# Cameras.net
KiCad netlist of a schematic drawn in Altium Designer
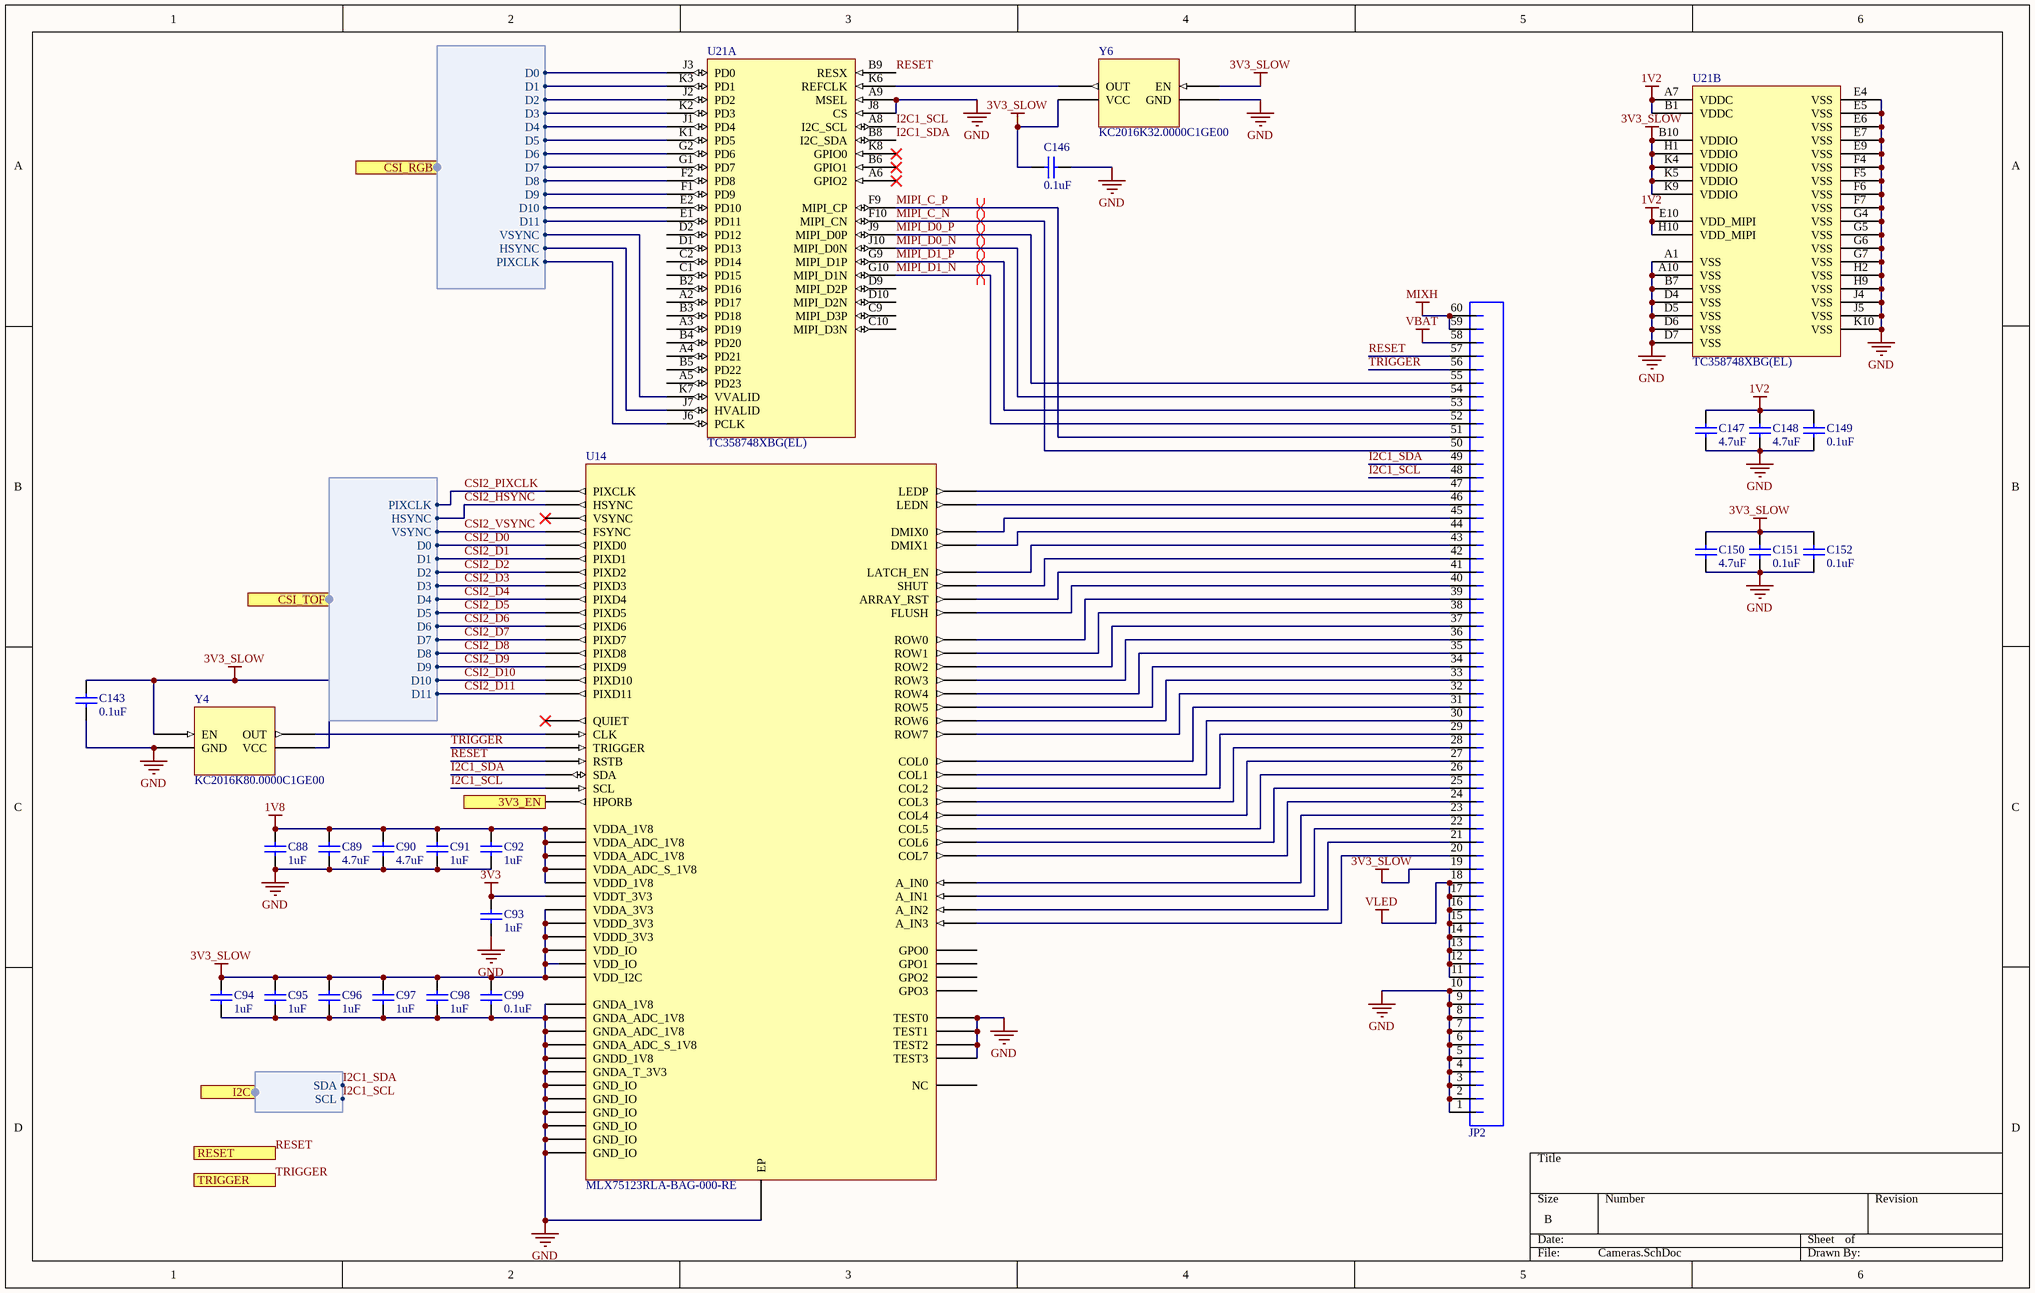
[diagram p0: Cameras.SchDoc]

(export (version "E")
  (design (tool "Eeschema 10.0.6"))
  (components
    (comp (ref "C88")
      (value "1uF")
      (footprint "C0402[1005X55]")
      (description "1uF 6.3V 10% 0402 (1005 Metric)")
      (fields (field (name "PARTNUMBER") "GRM155R70J105KA12D") (field (name "MANUFACTURER") "Murata"))
      (libsource (lib "Capacitors") (part "CAP_1uF_6.3V_0402_10%"))
    )
    (comp (ref "C89")
      (value "4.7uF")
      (footprint "C0402[1005X55]")
      (description "4.7uF 6.3V 20% 0402 (1005 Metric)")
      (fields (field (name "PARTNUMBER") "GRM155R60J475ME47D") (field (name "MANUFACTURER") "Murata"))
      (libsource (lib "Capacitors") (part "CAP_4.7uF_6.3V_0402_20%"))
    )
    (comp (ref "C90")
      (value "4.7uF")
      (footprint "C0402[1005X55]")
      (description "4.7uF 6.3V 20% 0402 (1005 Metric)")
      (fields (field (name "PARTNUMBER") "GRM155R60J475ME47D") (field (name "MANUFACTURER") "Murata"))
      (libsource (lib "Capacitors") (part "CAP_4.7uF_6.3V_0402_20%"))
    )
    (comp (ref "C91")
      (value "1uF")
      (footprint "C0402[1005X55]")
      (description "1uF 6.3V 10% 0402 (1005 Metric)")
      (fields (field (name "PARTNUMBER") "GRM155R70J105KA12D") (field (name "MANUFACTURER") "Murata"))
      (libsource (lib "Capacitors") (part "CAP_1uF_6.3V_0402_10%"))
    )
    (comp (ref "C92")
      (value "1uF")
      (footprint "C0402[1005X55]")
      (description "1uF 6.3V 10% 0402 (1005 Metric)")
      (fields (field (name "PARTNUMBER") "GRM155R70J105KA12D") (field (name "MANUFACTURER") "Murata"))
      (libsource (lib "Capacitors") (part "CAP_1uF_6.3V_0402_10%"))
    )
    (comp (ref "C93")
      (value "1uF")
      (footprint "C0402[1005X55]")
      (description "1uF 6.3V 10% 0402 (1005 Metric)")
      (fields (field (name "PARTNUMBER") "GRM155R70J105KA12D") (field (name "MANUFACTURER") "Murata"))
      (libsource (lib "Capacitors") (part "CAP_1uF_6.3V_0402_10%"))
    )
    (comp (ref "C94")
      (value "1uF")
      (footprint "C0402[1005X55]")
      (description "1uF 6.3V 10% 0402 (1005 Metric)")
      (fields (field (name "PARTNUMBER") "GRM155R70J105KA12D") (field (name "MANUFACTURER") "Murata"))
      (libsource (lib "Capacitors") (part "CAP_1uF_6.3V_0402_10%"))
    )
    (comp (ref "C95")
      (value "1uF")
      (footprint "C0402[1005X55]")
      (description "1uF 6.3V 10% 0402 (1005 Metric)")
      (fields (field (name "PARTNUMBER") "GRM155R70J105KA12D") (field (name "MANUFACTURER") "Murata"))
      (libsource (lib "Capacitors") (part "CAP_1uF_6.3V_0402_10%"))
    )
    (comp (ref "C96")
      (value "1uF")
      (footprint "C0402[1005X55]")
      (description "1uF 6.3V 10% 0402 (1005 Metric)")
      (fields (field (name "PARTNUMBER") "GRM155R70J105KA12D") (field (name "MANUFACTURER") "Murata"))
      (libsource (lib "Capacitors") (part "CAP_1uF_6.3V_0402_10%"))
    )
    (comp (ref "C97")
      (value "1uF")
      (footprint "C0402[1005X55]")
      (description "1uF 6.3V 10% 0402 (1005 Metric)")
      (fields (field (name "PARTNUMBER") "GRM155R70J105KA12D") (field (name "MANUFACTURER") "Murata"))
      (libsource (lib "Capacitors") (part "CAP_1uF_6.3V_0402_10%"))
    )
    (comp (ref "C98")
      (value "1uF")
      (footprint "C0402[1005X55]")
      (description "1uF 6.3V 10% 0402 (1005 Metric)")
      (fields (field (name "PARTNUMBER") "GRM155R70J105KA12D") (field (name "MANUFACTURER") "Murata"))
      (libsource (lib "Capacitors") (part "CAP_1uF_6.3V_0402_10%"))
    )
    (comp (ref "C99")
      (value "0.1uF")
      (footprint "C0402[1005X55]")
      (description "0.1uF 6.3V 10% 0402 (1005 Metric)")
      (fields (field (name "PARTNUMBER") "GRM155R70J104KA01D") (field (name "MANUFACTURER") "Murata"))
      (libsource (lib "Capacitors") (part "CAP_0.1uF_6.3V_0402_10%"))
    )
    (comp (ref "C143")
      (value "0.1uF")
      (footprint "C0402[1005X55]")
      (description "0.1uF 6.3V 10% 0402 (1005 Metric)")
      (fields (field (name "PARTNUMBER") "GRM155R70J104KA01D") (field (name "MANUFACTURER") "Murata"))
      (libsource (lib "Capacitors") (part "CAP_0.1uF_6.3V_0402_10%"))
    )
    (comp (ref "C146")
      (value "0.1uF")
      (footprint "C0402[1005X55]")
      (description "0.1uF 6.3V 10% 0402 (1005 Metric)")
      (fields (field (name "PARTNUMBER") "GRM155R70J104KA01D") (field (name "MANUFACTURER") "Murata"))
      (libsource (lib "Capacitors") (part "CAP_0.1uF_6.3V_0402_10%"))
    )
    (comp (ref "C147")
      (value "4.7uF")
      (footprint "C0402[1005X55]")
      (description "4.7uF 6.3V 20% 0402 (1005 Metric)")
      (fields (field (name "PARTNUMBER") "GRM155R60J475ME47D") (field (name "MANUFACTURER") "Murata"))
      (libsource (lib "Capacitors") (part "CAP_4.7uF_6.3V_0402_20%"))
    )
    (comp (ref "C148")
      (value "4.7uF")
      (footprint "C0402[1005X55]")
      (description "4.7uF 6.3V 20% 0402 (1005 Metric)")
      (fields (field (name "PARTNUMBER") "GRM155R60J475ME47D") (field (name "MANUFACTURER") "Murata"))
      (libsource (lib "Capacitors") (part "CAP_4.7uF_6.3V_0402_20%"))
    )
    (comp (ref "C149")
      (value "0.1uF")
      (footprint "C0402[1005X55]")
      (description "0.1uF 6.3V 10% 0402 (1005 Metric)")
      (fields (field (name "PARTNUMBER") "GRM155R70J104KA01D") (field (name "MANUFACTURER") "Murata"))
      (libsource (lib "Capacitors") (part "CAP_0.1uF_6.3V_0402_10%"))
    )
    (comp (ref "C150")
      (value "4.7uF")
      (footprint "C0402[1005X55]")
      (description "4.7uF 6.3V 20% 0402 (1005 Metric)")
      (fields (field (name "PARTNUMBER") "GRM155R60J475ME47D") (field (name "MANUFACTURER") "Murata"))
      (libsource (lib "Capacitors") (part "CAP_4.7uF_6.3V_0402_20%"))
    )
    (comp (ref "C151")
      (value "0.1uF")
      (footprint "C0402[1005X55]")
      (description "0.1uF 6.3V 10% 0402 (1005 Metric)")
      (fields (field (name "PARTNUMBER") "GRM155R70J104KA01D") (field (name "MANUFACTURER") "Murata"))
      (libsource (lib "Capacitors") (part "CAP_0.1uF_6.3V_0402_10%"))
    )
    (comp (ref "C152")
      (value "0.1uF")
      (footprint "C0402[1005X55]")
      (description "0.1uF 6.3V 10% 0402 (1005 Metric)")
      (fields (field (name "PARTNUMBER") "GRM155R70J104KA01D") (field (name "MANUFACTURER") "Murata"))
      (libsource (lib "Capacitors") (part "CAP_0.1uF_6.3V_0402_10%"))
    )
    (comp (ref "JP2")
      (value "JST_JMD_60_HORZ")
      (footprint "JST-JMD-60-SMD-HORZ")
      (fields
        (field (name "MANUFACTURER") "JST Sales America, Inc.")
        (field (name "PARTNUMBER") "60PS-JMDSS-G-1-TF")
      )
      (libsource (lib "Connectors") (part "JST_JMD_60_HORZ"))
    )
    (comp (ref "U14")
      (value "MLX75123RLA-BAG-000-RE")
      (footprint "AQFN-84")
      (description "Sensor Interface ToF Companion Chip")
      (fields (field (name "MANUFACTURER") "Melexis"))
      (libsource (lib "ICs") (part "MLX75123RLA-BAG-000-RE"))
    )
    (comp (ref "U21")
      (value "TC358748XBG(EL)")
      (footprint "BGA-80")
      (description "IC MIPI CSI2 TO PARALLEL 80VFBGA")
      (fields (field (name "MANUFACTURER") "Toshiba Semiconductor"))
      (libsource (lib "ICs") (part "TC358748XBG(EL)"))
    )
    (comp (ref "Y4")
      (value "KC2016K80.0000C1GE00")
      (footprint "KC2016K")
      (description "OSC XO 80.0000MHZ CMOS SMD")
      (fields (field (name "MANUFACTURER") "AVX"))
      (libsource (lib "Components") (part "KC2016K80.0000C1GE00"))
    )
    (comp (ref "Y6")
      (value "KC2016K32.0000C1GE00")
      (footprint "KC2016K")
      (description "OSC XO 32.0000MHZ CMOS SMD")
      (fields (field (name "MANUFACTURER") "Kyocera"))
      (libsource (lib "Components") (part "KC2016K32.0000C1GE00"))
    )
  )
  (nets
    (net (code "3") (name "/3V3_EN") (class "Default")
      (node (ref "U14") (pin "A19") (pinfunction "HPORB_A19") (pintype "output"))
    )
    (net (code "4") (name "/CSI2_D0") (class "Default")
      (node (ref "U14") (pin "A30") (pinfunction "PIXD0_A30") (pintype "output"))
    )
    (net (code "5") (name "/CSI2_D1") (class "Default")
      (node (ref "U14") (pin "B27") (pinfunction "PIXD1_B27") (pintype "output"))
    )
    (net (code "6") (name "/CSI2_D2") (class "Default")
      (node (ref "U14") (pin "A29") (pinfunction "PIXD2_A29") (pintype "output"))
    )
    (net (code "7") (name "/CSI2_D3") (class "Default")
      (node (ref "U14") (pin "B26") (pinfunction "PIXD3_B26") (pintype "output"))
    )
    (net (code "8") (name "/CSI2_D4") (class "Default")
      (node (ref "U14") (pin "A28") (pinfunction "PIXD4_A28") (pintype "output"))
    )
    (net (code "9") (name "/CSI2_D5") (class "Default")
      (node (ref "U14") (pin "B25") (pinfunction "PIXD5_B25") (pintype "output"))
    )
    (net (code "10") (name "/CSI2_D6") (class "Default")
      (node (ref "U14") (pin "A27") (pinfunction "PIXD6_A27") (pintype "output"))
    )
    (net (code "11") (name "/CSI2_D7") (class "Default")
      (node (ref "U14") (pin "B24") (pinfunction "PIXD7_B24") (pintype "output"))
    )
    (net (code "12") (name "/CSI2_D8") (class "Default")
      (node (ref "U14") (pin "A26") (pinfunction "PIXD8_A26") (pintype "output"))
    )
    (net (code "13") (name "/CSI2_D9") (class "Default")
      (node (ref "U14") (pin "B23") (pinfunction "PIXD9_B23") (pintype "output"))
    )
    (net (code "14") (name "/CSI2_D10") (class "Default")
      (node (ref "U14") (pin "A25") (pinfunction "PIXD10_A25") (pintype "output"))
    )
    (net (code "15") (name "/CSI2_D11") (class "Default")
      (node (ref "U14") (pin "B22") (pinfunction "PIXD11_B22") (pintype "output"))
    )
    (net (code "16") (name "/CSI2_HSYNC") (class "Default")
      (node (ref "U14") (pin "B29") (pinfunction "HSYNC_B29") (pintype "output"))
    )
    (net (code "17") (name "/CSI2_PIXCLK") (class "Default")
      (node (ref "U14") (pin "B28") (pinfunction "PIXCLK_B28") (pintype "output"))
    )
    (net (code "18") (name "/CSI2_VSYNC") (class "Default")
      (node (ref "U14") (pin "A31") (pinfunction "FSYNC_A31") (pintype "output"))
    )
    (net (code "19") (name "/I2C1_SCL") (class "Default")
      (node (ref "JP2") (pin "48") (pinfunction "48_48") (pintype "passive"))
      (node (ref "U14") (pin "A12") (pinfunction "SCL_A12") (pintype "input"))
      (node (ref "U21") (pin "A8") (pinfunction "I2C_SCL_A8") (pintype "bidirectional"))
    )
    (net (code "20") (name "/I2C1_SDA") (class "Default")
      (node (ref "JP2") (pin "49") (pinfunction "49_49") (pintype "passive"))
      (node (ref "U14") (pin "B11") (pinfunction "SDA_B11") (pintype "bidirectional"))
      (node (ref "U21") (pin "B8") (pinfunction "I2C_SDA_B8") (pintype "bidirectional"))
    )
    (net (code "21") (name "/MIPI_C_N") (class "Default")
      (node (ref "JP2") (pin "50") (pinfunction "50_50") (pintype "passive"))
      (node (ref "U21") (pin "F10") (pinfunction "MIPI_CN_F10") (pintype "bidirectional"))
    )
    (net (code "22") (name "/MIPI_C_P") (class "Default")
      (node (ref "JP2") (pin "51") (pinfunction "51_51") (pintype "passive"))
      (node (ref "U21") (pin "F9") (pinfunction "MIPI_CP_F9") (pintype "bidirectional"))
    )
    (net (code "23") (name "/MIPI_D0_N") (class "Default")
      (node (ref "JP2") (pin "54") (pinfunction "54_54") (pintype "passive"))
      (node (ref "U21") (pin "J10") (pinfunction "MIPI_D0N_J10") (pintype "bidirectional"))
    )
    (net (code "24") (name "/MIPI_D0_P") (class "Default")
      (node (ref "JP2") (pin "55") (pinfunction "55_55") (pintype "passive"))
      (node (ref "U21") (pin "J9") (pinfunction "MIPI_D0P_J9") (pintype "bidirectional"))
    )
    (net (code "25") (name "/MIPI_D1_N") (class "Default")
      (node (ref "JP2") (pin "52") (pinfunction "52_52") (pintype "passive"))
      (node (ref "U21") (pin "G10") (pinfunction "MIPI_D1N_G10") (pintype "bidirectional"))
    )
    (net (code "26") (name "/MIPI_D1_P") (class "Default")
      (node (ref "JP2") (pin "53") (pinfunction "53_53") (pintype "passive"))
      (node (ref "U21") (pin "G9") (pinfunction "MIPI_D1P_G9") (pintype "bidirectional"))
    )
    (net (code "27") (name "/RESET") (class "Default")
      (node (ref "JP2") (pin "57") (pinfunction "57_57") (pintype "passive"))
      (node (ref "U14") (pin "A14") (pinfunction "RSTB_A14") (pintype "input"))
      (node (ref "U21") (pin "B9") (pinfunction "RESX_B9") (pintype "input"))
    )
    (net (code "28") (name "/TRIGGER") (class "Default")
      (node (ref "JP2") (pin "56") (pinfunction "56_56") (pintype "passive"))
      (node (ref "U14") (pin "A13") (pinfunction "TRIGGER_A13") (pintype "input"))
    )
    (net (code "31") (name "1V2") (class "Default")
      (node (ref "C147") (pin "2") (pinfunction "2_2") (pintype "passive"))
      (node (ref "C148") (pin "2") (pinfunction "2_2") (pintype "passive"))
      (node (ref "C149") (pin "2") (pinfunction "2_2") (pintype "passive"))
      (node (ref "U21") (pin "A7") (pinfunction "VDDC_A7") (pintype "power_in"))
      (node (ref "U21") (pin "B1") (pinfunction "VDDC_B1") (pintype "power_in"))
      (node (ref "U21") (pin "E10") (pinfunction "VDD_MIPI_E10") (pintype "power_in"))
      (node (ref "U21") (pin "H10") (pinfunction "VDD_MIPI_H10") (pintype "power_in"))
    )
    (net (code "32") (name "1V8") (class "Default")
      (node (ref "C88") (pin "2") (pinfunction "2_2") (pintype "passive"))
      (node (ref "C89") (pin "2") (pinfunction "2_2") (pintype "passive"))
      (node (ref "C90") (pin "2") (pinfunction "2_2") (pintype "passive"))
      (node (ref "C91") (pin "2") (pinfunction "2_2") (pintype "passive"))
      (node (ref "C92") (pin "2") (pinfunction "2_2") (pintype "passive"))
      (node (ref "U14") (pin "A10") (pinfunction "VDDA_ADC_S_1V8_A10") (pintype "power_in"))
      (node (ref "U14") (pin "A9") (pinfunction "VDDA_ADC_1V8_A9") (pintype "power_in"))
      (node (ref "U14") (pin "B14") (pinfunction "VDDA_1V8_B14") (pintype "power_in"))
      (node (ref "U14") (pin "B20") (pinfunction "VDDD_1V8_B20") (pintype "power_in"))
      (node (ref "U14") (pin "B5") (pinfunction "VDDA_ADC_1V8_B5") (pintype "power_in"))
    )
    (net (code "33") (name "3V3") (class "Default")
      (node (ref "C93") (pin "2") (pinfunction "2_2") (pintype "passive"))
      (node (ref "U14") (pin "B17") (pinfunction "VDDT_3V3_B17") (pintype "power_in"))
    )
    (net (code "34") (name "3V3_SLOW") (class "Default")
      (node (ref "C143") (pin "2") (pinfunction "2_2") (pintype "passive"))
      (node (ref "C146") (pin "1") (pinfunction "1_1") (pintype "passive"))
      (node (ref "C150") (pin "2") (pinfunction "2_2") (pintype "passive"))
      (node (ref "C151") (pin "2") (pinfunction "2_2") (pintype "passive"))
      (node (ref "C152") (pin "2") (pinfunction "2_2") (pintype "passive"))
      (node (ref "C94") (pin "2") (pinfunction "2_2") (pintype "passive"))
      (node (ref "C95") (pin "2") (pinfunction "2_2") (pintype "passive"))
      (node (ref "C96") (pin "2") (pinfunction "2_2") (pintype "passive"))
      (node (ref "C97") (pin "2") (pinfunction "2_2") (pintype "passive"))
      (node (ref "C98") (pin "2") (pinfunction "2_2") (pintype "passive"))
      (node (ref "C99") (pin "2") (pinfunction "2_2") (pintype "passive"))
      (node (ref "JP2") (pin "19") (pinfunction "19_19") (pintype "passive"))
      (node (ref "U14") (pin "A36") (pinfunction "VDDD_3V3_A36") (pintype "power_in"))
      (node (ref "U14") (pin "B12") (pinfunction "VDD_I2C_B12") (pintype "power_in"))
      (node (ref "U14") (pin "B21") (pinfunction "VDD_IO_B21") (pintype "power_in"))
      (node (ref "U14") (pin "B30") (pinfunction "VDD_IO_B30") (pintype "power_in"))
      (node (ref "U14") (pin "B38") (pinfunction "VDDD_3V3_B38") (pintype "power_in"))
      (node (ref "U14") (pin "B4") (pinfunction "VDDA_3V3_B4") (pintype "power_in"))
      (node (ref "U21") (pin "B10") (pinfunction "VDDIO_B10") (pintype "power_in"))
      (node (ref "U21") (pin "H1") (pinfunction "VDDIO_H1") (pintype "power_in"))
      (node (ref "U21") (pin "K4") (pinfunction "VDDIO_K4") (pintype "power_in"))
      (node (ref "U21") (pin "K5") (pinfunction "VDDIO_K5") (pintype "power_in"))
      (node (ref "U21") (pin "K9") (pinfunction "VDDIO_K9") (pintype "power_in"))
      (node (ref "Y4") (pin "1") (pinfunction "EN_1") (pintype "input"))
      (node (ref "Y4") (pin "4") (pinfunction "VCC_4") (pintype "power_in"))
      (node (ref "Y6") (pin "1") (pinfunction "EN_1") (pintype "input"))
      (node (ref "Y6") (pin "4") (pinfunction "VCC_4") (pintype "power_in"))
    )
    (net (code "35") (name "GND") (class "Default")
      (node (ref "C143") (pin "1") (pinfunction "1_1") (pintype "passive"))
      (node (ref "C146") (pin "2") (pinfunction "2_2") (pintype "passive"))
      (node (ref "C147") (pin "1") (pinfunction "1_1") (pintype "passive"))
      (node (ref "C148") (pin "1") (pinfunction "1_1") (pintype "passive"))
      (node (ref "C149") (pin "1") (pinfunction "1_1") (pintype "passive"))
      (node (ref "C150") (pin "1") (pinfunction "1_1") (pintype "passive"))
      (node (ref "C151") (pin "1") (pinfunction "1_1") (pintype "passive"))
      (node (ref "C152") (pin "1") (pinfunction "1_1") (pintype "passive"))
      (node (ref "C88") (pin "1") (pinfunction "1_1") (pintype "passive"))
      (node (ref "C89") (pin "1") (pinfunction "1_1") (pintype "passive"))
      (node (ref "C90") (pin "1") (pinfunction "1_1") (pintype "passive"))
      (node (ref "C91") (pin "1") (pinfunction "1_1") (pintype "passive"))
      (node (ref "C92") (pin "1") (pinfunction "1_1") (pintype "passive"))
      (node (ref "C93") (pin "1") (pinfunction "1_1") (pintype "passive"))
      (node (ref "C94") (pin "1") (pinfunction "1_1") (pintype "passive"))
      (node (ref "C95") (pin "1") (pinfunction "1_1") (pintype "passive"))
      (node (ref "C96") (pin "1") (pinfunction "1_1") (pintype "passive"))
      (node (ref "C97") (pin "1") (pinfunction "1_1") (pintype "passive"))
      (node (ref "C98") (pin "1") (pinfunction "1_1") (pintype "passive"))
      (node (ref "C99") (pin "1") (pinfunction "1_1") (pintype "passive"))
      (node (ref "JP2") (pin "1") (pinfunction "1_1") (pintype "passive"))
      (node (ref "JP2") (pin "10") (pinfunction "10_10") (pintype "passive"))
      (node (ref "JP2") (pin "2") (pinfunction "2_2") (pintype "passive"))
      (node (ref "JP2") (pin "3") (pinfunction "3_3") (pintype "passive"))
      (node (ref "JP2") (pin "4") (pinfunction "4_4") (pintype "passive"))
      (node (ref "JP2") (pin "5") (pinfunction "5_5") (pintype "passive"))
      (node (ref "JP2") (pin "6") (pinfunction "6_6") (pintype "passive"))
      (node (ref "JP2") (pin "7") (pinfunction "7_7") (pintype "passive"))
      (node (ref "JP2") (pin "8") (pinfunction "8_8") (pintype "passive"))
      (node (ref "JP2") (pin "9") (pinfunction "9_9") (pintype "passive"))
      (node (ref "U14") (pin "A11") (pinfunction "TEST2_A11") (pintype "passive"))
      (node (ref "U14") (pin "A16") (pinfunction "GNDA_1V8_A16") (pintype "power_in"))
      (node (ref "U14") (pin "A17") (pinfunction "TEST0_A17") (pintype "passive"))
      (node (ref "U14") (pin "A18") (pinfunction "GNDA_T_3V3_A18") (pintype "power_in"))
      (node (ref "U14") (pin "A22") (pinfunction "GNDD_1V8_A22") (pintype "power_in"))
      (node (ref "U14") (pin "A24") (pinfunction "GND_IO_A24") (pintype "power_in"))
      (node (ref "U14") (pin "A33") (pinfunction "GND_IO_A33") (pintype "power_in"))
      (node (ref "U14") (pin "A41") (pinfunction "GND_IO_A41") (pintype "power_in"))
      (node (ref "U14") (pin "A5") (pinfunction "GNDA_ADC_1V8_A5") (pintype "power_in"))
      (node (ref "U14") (pin "A8") (pinfunction "GND_IO_A8") (pintype "power_in"))
      (node (ref "U14") (pin "B10") (pinfunction "TEST3_B10") (pintype "passive"))
      (node (ref "U14") (pin "B15") (pinfunction "GND_IO_B15") (pintype "power_in"))
      (node (ref "U14") (pin "B16") (pinfunction "TEST1_B16") (pintype "passive"))
      (node (ref "U14") (pin "B33") (pinfunction "GND_IO_B33") (pintype "power_in"))
      (node (ref "U14") (pin "B8") (pinfunction "GNDA_ADC_1V8_B8") (pintype "power_in"))
      (node (ref "U14") (pin "B9") (pinfunction "GNDA_ADC_S_1V8_B9") (pintype "power_in"))
      (node (ref "U14") (pin "EP") (pinfunction "EP_EP") (pintype "passive"))
      (node (ref "U21") (pin "A1") (pinfunction "VSS_A1") (pintype "power_in"))
      (node (ref "U21") (pin "A10") (pinfunction "VSS_A10") (pintype "power_in"))
      (node (ref "U21") (pin "A9") (pinfunction "MSEL_A9") (pintype "input"))
      (node (ref "U21") (pin "B7") (pinfunction "VSS_B7") (pintype "power_in"))
      (node (ref "U21") (pin "D4") (pinfunction "VSS_D4") (pintype "power_in"))
      (node (ref "U21") (pin "D5") (pinfunction "VSS_D5") (pintype "power_in"))
      (node (ref "U21") (pin "D6") (pinfunction "VSS_D6") (pintype "power_in"))
      (node (ref "U21") (pin "D7") (pinfunction "VSS_D7") (pintype "power_in"))
      (node (ref "U21") (pin "E4") (pinfunction "VSS_E4") (pintype "power_in"))
      (node (ref "U21") (pin "E5") (pinfunction "VSS_E5") (pintype "power_in"))
      (node (ref "U21") (pin "E6") (pinfunction "VSS_E6") (pintype "power_in"))
      (node (ref "U21") (pin "E7") (pinfunction "VSS_E7") (pintype "power_in"))
      (node (ref "U21") (pin "E9") (pinfunction "VSS_E9") (pintype "power_in"))
      (node (ref "U21") (pin "F4") (pinfunction "VSS_F4") (pintype "power_in"))
      (node (ref "U21") (pin "F5") (pinfunction "VSS_F5") (pintype "power_in"))
      (node (ref "U21") (pin "F6") (pinfunction "VSS_F6") (pintype "power_in"))
      (node (ref "U21") (pin "F7") (pinfunction "VSS_F7") (pintype "power_in"))
      (node (ref "U21") (pin "G4") (pinfunction "VSS_G4") (pintype "power_in"))
      (node (ref "U21") (pin "G5") (pinfunction "VSS_G5") (pintype "power_in"))
      (node (ref "U21") (pin "G6") (pinfunction "VSS_G6") (pintype "power_in"))
      (node (ref "U21") (pin "G7") (pinfunction "VSS_G7") (pintype "power_in"))
      (node (ref "U21") (pin "H2") (pinfunction "VSS_H2") (pintype "power_in"))
      (node (ref "U21") (pin "H9") (pinfunction "VSS_H9") (pintype "power_in"))
      (node (ref "U21") (pin "J4") (pinfunction "VSS_J4") (pintype "power_in"))
      (node (ref "U21") (pin "J5") (pinfunction "VSS_J5") (pintype "power_in"))
      (node (ref "U21") (pin "J8") (pinfunction "CS_J8") (pintype "input"))
      (node (ref "U21") (pin "K10") (pinfunction "VSS_K10") (pintype "power_in"))
      (node (ref "Y4") (pin "2") (pinfunction "GND_2") (pintype "power_in"))
      (node (ref "Y6") (pin "2") (pinfunction "GND_2") (pintype "power_in"))
    )
    (net (code "36") (name "MIXH") (class "Default")
      (node (ref "JP2") (pin "59") (pinfunction "59_59") (pintype "passive"))
      (node (ref "JP2") (pin "60") (pinfunction "60_60") (pintype "passive"))
    )
    (net (code "37") (name "Net-(U14-ARRAY_RST)") (class "Default")
      (node (ref "JP2") (pin "41") (pinfunction "41_41") (pintype "passive"))
      (node (ref "U14") (pin "A3") (pinfunction "ARRAY_RST_A3") (pintype "output"))
    )
    (net (code "38") (name "Net-(U14-A_IN0)") (class "Default")
      (node (ref "JP2") (pin "23") (pinfunction "23_23") (pintype "passive"))
      (node (ref "U14") (pin "B6") (pinfunction "A_IN0_B6") (pintype "input"))
    )
    (net (code "39") (name "Net-(U14-A_IN1)") (class "Default")
      (node (ref "JP2") (pin "22") (pinfunction "22_22") (pintype "passive"))
      (node (ref "U14") (pin "A6") (pinfunction "A_IN1_A6") (pintype "input"))
    )
    (net (code "40") (name "Net-(U14-A_IN2)") (class "Default")
      (node (ref "JP2") (pin "21") (pinfunction "21_21") (pintype "passive"))
      (node (ref "U14") (pin "A7") (pinfunction "A_IN2_A7") (pintype "input"))
    )
    (net (code "41") (name "Net-(U14-A_IN3)") (class "Default")
      (node (ref "JP2") (pin "20") (pinfunction "20_20") (pintype "passive"))
      (node (ref "U14") (pin "B7") (pinfunction "A_IN3_B7") (pintype "input"))
    )
    (net (code "42") (name "Net-(U14-CLK)") (class "Default")
      (node (ref "U14") (pin "B13") (pinfunction "CLK_B13") (pintype "input"))
      (node (ref "Y4") (pin "3") (pinfunction "OUT_3") (pintype "output"))
    )
    (net (code "43") (name "Net-(U14-COL0)") (class "Default")
      (node (ref "JP2") (pin "31") (pinfunction "31_31") (pintype "passive"))
      (node (ref "U14") (pin "B37") (pinfunction "COL0_B37") (pintype "output"))
    )
    (net (code "44") (name "Net-(U14-COL1)") (class "Default")
      (node (ref "JP2") (pin "30") (pinfunction "30_30") (pintype "passive"))
      (node (ref "U14") (pin "A40") (pinfunction "COL1_A40") (pintype "output"))
    )
    (net (code "45") (name "Net-(U14-COL2)") (class "Default")
      (node (ref "JP2") (pin "29") (pinfunction "29_29") (pintype "passive"))
      (node (ref "U14") (pin "B36") (pinfunction "COL2_B36") (pintype "output"))
    )
    (net (code "46") (name "Net-(U14-COL3)") (class "Default")
      (node (ref "JP2") (pin "28") (pinfunction "28_28") (pintype "passive"))
      (node (ref "U14") (pin "A39") (pinfunction "COL3_A39") (pintype "output"))
    )
    (net (code "47") (name "Net-(U14-COL4)") (class "Default")
      (node (ref "JP2") (pin "27") (pinfunction "27_27") (pintype "passive"))
      (node (ref "U14") (pin "B35") (pinfunction "COL4_B35") (pintype "output"))
    )
    (net (code "48") (name "Net-(U14-COL5)") (class "Default")
      (node (ref "JP2") (pin "26") (pinfunction "26_26") (pintype "passive"))
      (node (ref "U14") (pin "A38") (pinfunction "COL5_A38") (pintype "output"))
    )
    (net (code "49") (name "Net-(U14-COL6)") (class "Default")
      (node (ref "JP2") (pin "25") (pinfunction "25_25") (pintype "passive"))
      (node (ref "U14") (pin "B34") (pinfunction "COL6_B34") (pintype "output"))
    )
    (net (code "50") (name "Net-(U14-COL7)") (class "Default")
      (node (ref "JP2") (pin "24") (pinfunction "24_24") (pintype "passive"))
      (node (ref "U14") (pin "A37") (pinfunction "COL7_A37") (pintype "output"))
    )
    (net (code "51") (name "Net-(U14-DMIX0)") (class "Default")
      (node (ref "JP2") (pin "45") (pinfunction "45_45") (pintype "passive"))
      (node (ref "U14") (pin "A35") (pinfunction "DMIX0_A35") (pintype "output"))
    )
    (net (code "52") (name "Net-(U14-DMIX1)") (class "Default")
      (node (ref "JP2") (pin "44") (pinfunction "44_44") (pintype "passive"))
      (node (ref "U14") (pin "B32") (pinfunction "DMIX1_B32") (pintype "output"))
    )
    (net (code "53") (name "Net-(U14-FLUSH)") (class "Default")
      (node (ref "JP2") (pin "40") (pinfunction "40_40") (pintype "passive"))
      (node (ref "U14") (pin "B3") (pinfunction "FLUSH_B3") (pintype "output"))
    )
    (net (code "54") (name "Net-(U14-LATCH_EN)") (class "Default")
      (node (ref "JP2") (pin "43") (pinfunction "43_43") (pintype "passive"))
      (node (ref "U14") (pin "A4") (pinfunction "LATCH_EN_A4") (pintype "output"))
    )
    (net (code "55") (name "Net-(U14-LEDN)") (class "Default")
      (node (ref "JP2") (pin "46") (pinfunction "46_46") (pintype "passive"))
      (node (ref "U14") (pin "A34") (pinfunction "LEDN_A34") (pintype "output"))
    )
    (net (code "56") (name "Net-(U14-LEDP)") (class "Default")
      (node (ref "JP2") (pin "47") (pinfunction "47_47") (pintype "passive"))
      (node (ref "U14") (pin "B31") (pinfunction "LEDP_B31") (pintype "output"))
    )
    (net (code "57") (name "Net-(U14-ROW0)") (class "Default")
      (node (ref "JP2") (pin "39") (pinfunction "39_39") (pintype "passive"))
      (node (ref "U14") (pin "A42") (pinfunction "ROW0_A42") (pintype "output"))
    )
    (net (code "58") (name "Net-(U14-ROW1)") (class "Default")
      (node (ref "JP2") (pin "38") (pinfunction "38_38") (pintype "passive"))
      (node (ref "U14") (pin "B39") (pinfunction "ROW1_B39") (pintype "output"))
    )
    (net (code "59") (name "Net-(U14-ROW2)") (class "Default")
      (node (ref "JP2") (pin "37") (pinfunction "37_37") (pintype "passive"))
      (node (ref "U14") (pin "A43") (pinfunction "ROW2_A43") (pintype "output"))
    )
    (net (code "60") (name "Net-(U14-ROW3)") (class "Default")
      (node (ref "JP2") (pin "36") (pinfunction "36_36") (pintype "passive"))
      (node (ref "U14") (pin "B40") (pinfunction "ROW3_B40") (pintype "output"))
    )
    (net (code "61") (name "Net-(U14-ROW4)") (class "Default")
      (node (ref "JP2") (pin "35") (pinfunction "35_35") (pintype "passive"))
      (node (ref "U14") (pin "A44") (pinfunction "ROW4_A44") (pintype "output"))
    )
    (net (code "62") (name "Net-(U14-ROW5)") (class "Default")
      (node (ref "JP2") (pin "34") (pinfunction "34_34") (pintype "passive"))
      (node (ref "U14") (pin "A1") (pinfunction "ROW5_A1") (pintype "output"))
    )
    (net (code "63") (name "Net-(U14-ROW6)") (class "Default")
      (node (ref "JP2") (pin "33") (pinfunction "33_33") (pintype "passive"))
      (node (ref "U14") (pin "B1") (pinfunction "ROW6_B1") (pintype "output"))
    )
    (net (code "64") (name "Net-(U14-ROW7)") (class "Default")
      (node (ref "JP2") (pin "32") (pinfunction "32_32") (pintype "passive"))
      (node (ref "U14") (pin "A2") (pinfunction "ROW7_A2") (pintype "output"))
    )
    (net (code "65") (name "Net-(U14-SHUT)") (class "Default")
      (node (ref "JP2") (pin "42") (pinfunction "42_42") (pintype "passive"))
      (node (ref "U14") (pin "B2") (pinfunction "SHUT_B2") (pintype "output"))
    )
    (net (code "66") (name "Net-(U21A-REFCLK)") (class "Default")
      (node (ref "U21") (pin "K6") (pinfunction "REFCLK_K6") (pintype "input"))
      (node (ref "Y6") (pin "3") (pinfunction "OUT_3") (pintype "output"))
    )
    (net (code "67") (name "VBAT") (class "Default")
      (node (ref "JP2") (pin "58") (pinfunction "58_58") (pintype "passive"))
    )
    (net (code "68") (name "VLED") (class "Default")
      (node (ref "JP2") (pin "11") (pinfunction "11_11") (pintype "passive"))
      (node (ref "JP2") (pin "12") (pinfunction "12_12") (pintype "passive"))
      (node (ref "JP2") (pin "13") (pinfunction "13_13") (pintype "passive"))
      (node (ref "JP2") (pin "14") (pinfunction "14_14") (pintype "passive"))
      (node (ref "JP2") (pin "15") (pinfunction "15_15") (pintype "passive"))
      (node (ref "JP2") (pin "16") (pinfunction "16_16") (pintype "passive"))
      (node (ref "JP2") (pin "17") (pinfunction "17_17") (pintype "passive"))
      (node (ref "JP2") (pin "18") (pinfunction "18_18") (pintype "passive"))
    )
    (net (code "69") (name "unconnected-(U14-GPO0-PadB18)") (class "Default")
      (node (ref "U14") (pin "B18") (pinfunction "GPO0_B18") (pintype "passive"))
    )
    (net (code "70") (name "unconnected-(U14-GPO1-PadA20)") (class "Default")
      (node (ref "U14") (pin "A20") (pinfunction "GPO1_A20") (pintype "passive"))
    )
    (net (code "71") (name "unconnected-(U14-GPO2-PadB19)") (class "Default")
      (node (ref "U14") (pin "B19") (pinfunction "GPO2_B19") (pintype "passive"))
    )
    (net (code "72") (name "unconnected-(U14-GPO3-PadA21)") (class "Default")
      (node (ref "U14") (pin "A21") (pinfunction "GPO3_A21") (pintype "passive"))
    )
    (net (code "73") (name "unconnected-(U14-NC-PadA23)") (class "Default")
      (node (ref "U14") (pin "A23") (pinfunction "NC_A23") (pintype "passive"))
    )
    (net (code "74") (name "unconnected-(U14-QUIET-PadA15)") (class "Default")
      (node (ref "U14") (pin "A15") (pinfunction "QUIET_A15") (pintype "output+no_connect"))
    )
    (net (code "75") (name "unconnected-(U14-VSYNC-PadA32)") (class "Default")
      (node (ref "U14") (pin "A32") (pinfunction "VSYNC_A32") (pintype "output+no_connect"))
    )
    (net (code "76") (name "unconnected-(U21A-GPIO0-PadK8)") (class "Default")
      (node (ref "U21") (pin "K8") (pinfunction "GPIO0_K8") (pintype "input+no_connect"))
    )
    (net (code "77") (name "unconnected-(U21A-GPIO1-PadB6)") (class "Default")
      (node (ref "U21") (pin "B6") (pinfunction "GPIO1_B6") (pintype "input+no_connect"))
    )
    (net (code "78") (name "unconnected-(U21A-GPIO2-PadA6)") (class "Default")
      (node (ref "U21") (pin "A6") (pinfunction "GPIO2_A6") (pintype "input+no_connect"))
    )
    (net (code "79") (name "unconnected-(U21A-HVALID-PadJ7)") (class "Default")
      (node (ref "U21") (pin "J7") (pinfunction "HVALID_J7") (pintype "bidirectional"))
    )
    (net (code "80") (name "unconnected-(U21A-MIPI_D2N-PadD10)") (class "Default")
      (node (ref "U21") (pin "D10") (pinfunction "MIPI_D2N_D10") (pintype "bidirectional"))
    )
    (net (code "81") (name "unconnected-(U21A-MIPI_D2P-PadD9)") (class "Default")
      (node (ref "U21") (pin "D9") (pinfunction "MIPI_D2P_D9") (pintype "bidirectional"))
    )
    (net (code "82") (name "unconnected-(U21A-MIPI_D3N-PadC10)") (class "Default")
      (node (ref "U21") (pin "C10") (pinfunction "MIPI_D3N_C10") (pintype "bidirectional"))
    )
    (net (code "83") (name "unconnected-(U21A-MIPI_D3P-PadC9)") (class "Default")
      (node (ref "U21") (pin "C9") (pinfunction "MIPI_D3P_C9") (pintype "bidirectional"))
    )
    (net (code "84") (name "unconnected-(U21A-PCLK-PadJ6)") (class "Default")
      (node (ref "U21") (pin "J6") (pinfunction "PCLK_J6") (pintype "bidirectional"))
    )
    (net (code "85") (name "unconnected-(U21A-PD0-PadJ3)") (class "Default")
      (node (ref "U21") (pin "J3") (pinfunction "PD0_J3") (pintype "bidirectional"))
    )
    (net (code "86") (name "unconnected-(U21A-PD1-PadK3)") (class "Default")
      (node (ref "U21") (pin "K3") (pinfunction "PD1_K3") (pintype "bidirectional"))
    )
    (net (code "87") (name "unconnected-(U21A-PD2-PadJ2)") (class "Default")
      (node (ref "U21") (pin "J2") (pinfunction "PD2_J2") (pintype "bidirectional"))
    )
    (net (code "88") (name "unconnected-(U21A-PD3-PadK2)") (class "Default")
      (node (ref "U21") (pin "K2") (pinfunction "PD3_K2") (pintype "bidirectional"))
    )
    (net (code "89") (name "unconnected-(U21A-PD4-PadJ1)") (class "Default")
      (node (ref "U21") (pin "J1") (pinfunction "PD4_J1") (pintype "bidirectional"))
    )
    (net (code "90") (name "unconnected-(U21A-PD5-PadK1)") (class "Default")
      (node (ref "U21") (pin "K1") (pinfunction "PD5_K1") (pintype "bidirectional"))
    )
    (net (code "91") (name "unconnected-(U21A-PD6-PadG2)") (class "Default")
      (node (ref "U21") (pin "G2") (pinfunction "PD6_G2") (pintype "bidirectional"))
    )
    (net (code "92") (name "unconnected-(U21A-PD7-PadG1)") (class "Default")
      (node (ref "U21") (pin "G1") (pinfunction "PD7_G1") (pintype "bidirectional"))
    )
    (net (code "93") (name "unconnected-(U21A-PD8-PadF2)") (class "Default")
      (node (ref "U21") (pin "F2") (pinfunction "PD8_F2") (pintype "bidirectional"))
    )
    (net (code "94") (name "unconnected-(U21A-PD9-PadF1)") (class "Default")
      (node (ref "U21") (pin "F1") (pinfunction "PD9_F1") (pintype "bidirectional"))
    )
    (net (code "95") (name "unconnected-(U21A-PD10-PadE2)") (class "Default")
      (node (ref "U21") (pin "E2") (pinfunction "PD10_E2") (pintype "bidirectional"))
    )
    (net (code "96") (name "unconnected-(U21A-PD11-PadE1)") (class "Default")
      (node (ref "U21") (pin "E1") (pinfunction "PD11_E1") (pintype "bidirectional"))
    )
    (net (code "97") (name "unconnected-(U21A-PD12-PadD2)") (class "Default")
      (node (ref "U21") (pin "D2") (pinfunction "PD12_D2") (pintype "bidirectional"))
    )
    (net (code "98") (name "unconnected-(U21A-PD13-PadD1)") (class "Default")
      (node (ref "U21") (pin "D1") (pinfunction "PD13_D1") (pintype "bidirectional"))
    )
    (net (code "99") (name "unconnected-(U21A-PD14-PadC2)") (class "Default")
      (node (ref "U21") (pin "C2") (pinfunction "PD14_C2") (pintype "bidirectional"))
    )
    (net (code "100") (name "unconnected-(U21A-PD15-PadC1)") (class "Default")
      (node (ref "U21") (pin "C1") (pinfunction "PD15_C1") (pintype "bidirectional"))
    )
    (net (code "101") (name "unconnected-(U21A-PD16-PadB2)") (class "Default")
      (node (ref "U21") (pin "B2") (pinfunction "PD16_B2") (pintype "bidirectional"))
    )
    (net (code "102") (name "unconnected-(U21A-PD17-PadA2)") (class "Default")
      (node (ref "U21") (pin "A2") (pinfunction "PD17_A2") (pintype "bidirectional"))
    )
    (net (code "103") (name "unconnected-(U21A-PD18-PadB3)") (class "Default")
      (node (ref "U21") (pin "B3") (pinfunction "PD18_B3") (pintype "bidirectional"))
    )
    (net (code "104") (name "unconnected-(U21A-PD19-PadA3)") (class "Default")
      (node (ref "U21") (pin "A3") (pinfunction "PD19_A3") (pintype "bidirectional"))
    )
    (net (code "105") (name "unconnected-(U21A-PD20-PadB4)") (class "Default")
      (node (ref "U21") (pin "B4") (pinfunction "PD20_B4") (pintype "bidirectional"))
    )
    (net (code "106") (name "unconnected-(U21A-PD21-PadA4)") (class "Default")
      (node (ref "U21") (pin "A4") (pinfunction "PD21_A4") (pintype "bidirectional"))
    )
    (net (code "107") (name "unconnected-(U21A-PD22-PadB5)") (class "Default")
      (node (ref "U21") (pin "B5") (pinfunction "PD22_B5") (pintype "bidirectional"))
    )
    (net (code "108") (name "unconnected-(U21A-PD23-PadA5)") (class "Default")
      (node (ref "U21") (pin "A5") (pinfunction "PD23_A5") (pintype "bidirectional"))
    )
    (net (code "109") (name "unconnected-(U21A-VVALID-PadK7)") (class "Default")
      (node (ref "U21") (pin "K7") (pinfunction "VVALID_K7") (pintype "bidirectional"))
    )
  )
)
